# Microcontroller.net
KiCad netlist of a schematic drawn in Altium Designer
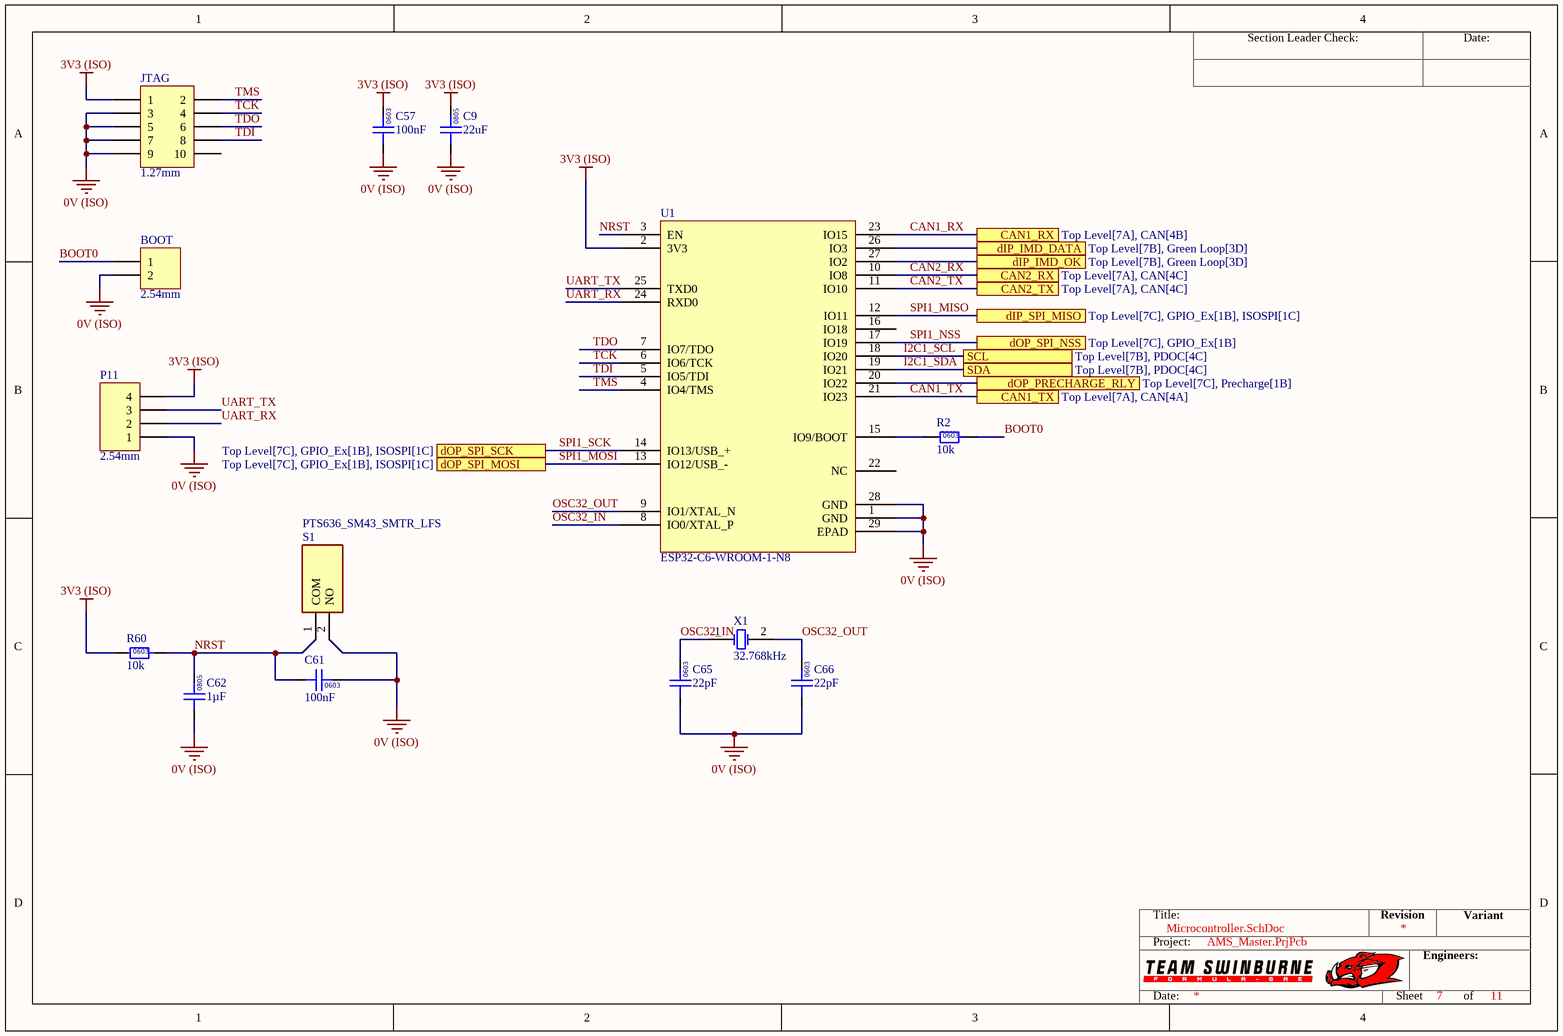
[diagram p0: Microcontroller.SchDoc]

(export (version "E")
  (design (tool "Eeschema 10.0.6"))
  (components
    (comp (ref "BOOT")
      (value "2.54mm")
      (footprint "TH 2.54mm Header 1x2")
      (fields (field (name "PART NUMBER") "TH 2.54mm Header 1x2") (field (name "CONTACT") "NA"))
      (libsource (lib "ts_standard_connectors") (part "Header 1x2"))
    )
    (comp (ref "C9")
      (value "22uF")
      (footprint "0805")
      (fields
        (field (name "PART NUMBER") "GRM21BR61A226ME51L")
        (field (name "MANUFACTURER") "muRata")
        (field (name "TOLERANCE") "20%")
      )
      (libsource (lib "ts_standard_library") (part "Capacitor 0805"))
    )
    (comp (ref "C57")
      (value "100nF")
      (footprint "0603")
      (fields
        (field (name "PART NUMBER") "GCM188L81H104KA57D")
        (field (name "MANUFACTURER") "muRata")
        (field (name "TOLERANCE") "±10%")
      )
      (libsource (lib "ts_standard_library") (part "Capacitor 0603"))
    )
    (comp (ref "C61")
      (value "100nF")
      (footprint "0603")
      (fields
        (field (name "PART NUMBER") "GCM188L81H104KA57D")
        (field (name "MANUFACTURER") "muRata")
        (field (name "TOLERANCE") "±10%")
      )
      (libsource (lib "ts_standard_library") (part "Capacitor 0603"))
    )
    (comp (ref "C62")
      (value "1µF")
      (footprint "0805")
      (fields
        (field (name "PART NUMBER") "GCM21BR71H105KA03L")
        (field (name "MANUFACTURER") "muRata")
        (field (name "TOLERANCE") "±10%")
      )
      (libsource (lib "ts_standard_library") (part "Capacitor 0805"))
    )
    (comp (ref "C65")
      (value "22pF")
      (footprint "0603")
      (fields
        (field (name "PART NUMBER") "GRM0335C1H220JA01D")
        (field (name "MANUFACTURER") "Murata Electronics")
        (field (name "TOLERANCE") "±5%")
      )
      (libsource (lib "ts_standard_library") (part "Capacitor 0603"))
    )
    (comp (ref "C66")
      (value "22pF")
      (footprint "0603")
      (fields
        (field (name "PART NUMBER") "GRM0335C1H220JA01D")
        (field (name "MANUFACTURER") "Murata Electronics")
        (field (name "TOLERANCE") "±5%")
      )
      (libsource (lib "ts_standard_library") (part "Capacitor 0603"))
    )
    (comp (ref "JTAG")
      (value "1.27mm")
      (footprint "3221-10-0300-00")
      (fields
        (field (name "PART NUMBER") "SMD 1.27mm Header 2x5 (3221-10-0300-00)")
        (field (name "CONTACT") "NA")
      )
      (libsource (lib "ts_standard_connectors") (part "Header 2x5"))
    )
    (comp (ref "P11")
      (value "2.54mm")
      (footprint "TH 2.54mm Header 1x4")
      (fields (field (name "PART NUMBER") "TH 2.54mm Header 1x4") (field (name "CONTACT") "NA"))
      (libsource (lib "ts_standard_connectors") (part "Header 1x4"))
    )
    (comp (ref "R2")
      (value "10k")
      (footprint "0603")
      (fields
        (field (name "PART NUMBER") "RC0603FR-0710KL")
        (field (name "MANUFACTURER") "YAGEO")
        (field (name "TOLERANCE") "0.01")
      )
      (libsource (lib "ts_standard_library") (part "Resistor 0603"))
    )
    (comp (ref "R60")
      (value "10k")
      (footprint "0603")
      (fields
        (field (name "PART NUMBER") "RC0603FR-0710KL")
        (field (name "MANUFACTURER") "YAGEO")
        (field (name "TOLERANCE") "0.01")
      )
      (libsource (lib "ts_standard_library") (part "Resistor 0603"))
    )
    (comp (ref "S1")
      (value "PTS636_SM43_SMTR_LFS")
      (footprint "SamacSys:PTS636SM43SMTRLFS")
      (description "Switch")
      (fields
        (field (name "MANUFACTURER_PART_NUMBER") "PTS636 SM43 SMTR LFS")
        (field (name "MOUSER PART NUMBER") "611-PTS636SM43SMTRLF")
      )
      (libsource (lib "*") (part "PTS636_SM43_SMTR_LFS"))
    )
    (comp (ref "U1")
      (value "ESP32-C6-WROOM-1-N8")
      (footprint "ESP32-C6-WROOM-1-N8")
      (description "RF TXRX MOD BT WIFI PCB TH SMD")
      (fields (field (name "MANUFACTURER") "Espressif"))
      (libsource (lib "ts_standard_library") (part "ESP32-C6-WROOM-1-N8"))
    )
    (comp (ref "X1")
      (value "32.768kHz")
      (footprint "EPSON 2-SMD")
      (fields
        (field (name "PART NUMBER") "FC-135 32.7680KA-A5")
        (field (name "MANUFACTURER") "EPSON")
        (field (name "DIGIKEY PART NUMBER") "SER4103TR-ND")
      )
      (libsource (lib "ts_standard_library") (part "Crystal"))
    )
  )
  (nets
    (net (code "1") (name "/BOOT0") (class "Default")
      (node (ref "BOOT") (pin "1") (pinfunction "1_1") (pintype "passive"))
      (node (ref "R2") (pin "2") (pinfunction "2_2") (pintype "passive"))
    )
    (net (code "2") (name "/CAN1_RX") (class "Default")
      (node (ref "U1") (pin "23") (pinfunction "IO15_23") (pintype "passive"))
    )
    (net (code "3") (name "/CAN1_TX") (class "Default")
      (node (ref "U1") (pin "21") (pinfunction "IO23_21") (pintype "passive"))
    )
    (net (code "4") (name "/CAN2_RX") (class "Default")
      (node (ref "U1") (pin "10") (pinfunction "IO8_10") (pintype "passive"))
    )
    (net (code "5") (name "/CAN2_TX") (class "Default")
      (node (ref "U1") (pin "11") (pinfunction "IO10_11") (pintype "passive"))
    )
    (net (code "6") (name "/I2C1_SCL") (class "Default")
      (node (ref "U1") (pin "18") (pinfunction "IO20_18") (pintype "passive"))
    )
    (net (code "7") (name "/I2C1_SDA") (class "Default")
      (node (ref "U1") (pin "19") (pinfunction "IO21_19") (pintype "passive"))
    )
    (net (code "8") (name "/NRST") (class "Default")
      (node (ref "C61") (pin "1") (pinfunction "1_1") (pintype "passive"))
      (node (ref "C62") (pin "2") (pinfunction "2_2") (pintype "passive"))
      (node (ref "R60") (pin "2") (pinfunction "2_2") (pintype "passive"))
      (node (ref "S1") (pin "1") (pinfunction "COM_1") (pintype "passive"))
      (node (ref "U1") (pin "3") (pinfunction "EN_3") (pintype "passive"))
    )
    (net (code "9") (name "/OSC32_IN") (class "Default")
      (node (ref "C65") (pin "2") (pinfunction "2_2") (pintype "passive"))
      (node (ref "U1") (pin "8") (pinfunction "IO0/XTAL_P_8") (pintype "passive"))
      (node (ref "X1") (pin "1") (pinfunction "OSC1_1") (pintype "passive"))
    )
    (net (code "10") (name "/OSC32_OUT") (class "Default")
      (node (ref "C66") (pin "2") (pinfunction "2_2") (pintype "passive"))
      (node (ref "U1") (pin "9") (pinfunction "IO1/XTAL_N_9") (pintype "passive"))
      (node (ref "X1") (pin "2") (pinfunction "OSC2_2") (pintype "passive"))
    )
    (net (code "11") (name "/SPI1_MISO") (class "Default")
      (node (ref "U1") (pin "12") (pinfunction "IO11_12") (pintype "passive"))
    )
    (net (code "12") (name "/SPI1_MOSI") (class "Default")
      (node (ref "U1") (pin "13") (pinfunction "IO12/USB_-_13") (pintype "passive"))
    )
    (net (code "13") (name "/SPI1_NSS") (class "Default")
      (node (ref "U1") (pin "17") (pinfunction "IO19_17") (pintype "passive"))
    )
    (net (code "14") (name "/SPI1_SCK") (class "Default")
      (node (ref "U1") (pin "14") (pinfunction "IO13/USB_+_14") (pintype "passive"))
    )
    (net (code "15") (name "/TCK") (class "Default")
      (node (ref "JTAG") (pin "4") (pinfunction "4_4") (pintype "passive"))
      (node (ref "U1") (pin "6") (pinfunction "IO6/TCK_6") (pintype "passive"))
    )
    (net (code "16") (name "/TDI") (class "Default")
      (node (ref "JTAG") (pin "8") (pinfunction "8_8") (pintype "passive"))
      (node (ref "U1") (pin "5") (pinfunction "IO5/TDI_5") (pintype "passive"))
    )
    (net (code "17") (name "/TDO") (class "Default")
      (node (ref "JTAG") (pin "6") (pinfunction "6_6") (pintype "passive"))
      (node (ref "U1") (pin "7") (pinfunction "IO7/TDO_7") (pintype "passive"))
    )
    (net (code "18") (name "/TMS") (class "Default")
      (node (ref "JTAG") (pin "2") (pinfunction "2_2") (pintype "passive"))
      (node (ref "U1") (pin "4") (pinfunction "IO4/TMS_4") (pintype "passive"))
    )
    (net (code "19") (name "/UART_RX") (class "Default")
      (node (ref "P11") (pin "2") (pinfunction "2_2") (pintype "passive"))
      (node (ref "U1") (pin "24") (pinfunction "RXD0_24") (pintype "passive"))
    )
    (net (code "20") (name "/UART_TX") (class "Default")
      (node (ref "P11") (pin "3") (pinfunction "3_3") (pintype "passive"))
      (node (ref "U1") (pin "25") (pinfunction "TXD0_25") (pintype "passive"))
    )
    (net (code "21") (name "/dIP_IMD_DATA") (class "Default")
      (node (ref "U1") (pin "26") (pinfunction "IO3_26") (pintype "passive"))
    )
    (net (code "22") (name "/dIP_IMD_OK") (class "Default")
      (node (ref "U1") (pin "27") (pinfunction "IO2_27") (pintype "passive"))
    )
    (net (code "23") (name "/dOP_PRECHARGE_RLY") (class "Default")
      (node (ref "U1") (pin "20") (pinfunction "IO22_20") (pintype "passive"))
    )
    (net (code "24") (name "0V (ISO)") (class "Default")
      (node (ref "BOOT") (pin "2") (pinfunction "2_2") (pintype "passive"))
      (node (ref "C57") (pin "1") (pinfunction "1_1") (pintype "passive"))
      (node (ref "C61") (pin "2") (pinfunction "2_2") (pintype "passive"))
      (node (ref "C62") (pin "1") (pinfunction "1_1") (pintype "passive"))
      (node (ref "C65") (pin "1") (pinfunction "1_1") (pintype "passive"))
      (node (ref "C66") (pin "1") (pinfunction "1_1") (pintype "passive"))
      (node (ref "C9") (pin "1") (pinfunction "1_1") (pintype "passive"))
      (node (ref "JTAG") (pin "3") (pinfunction "3_3") (pintype "passive"))
      (node (ref "JTAG") (pin "5") (pinfunction "5_5") (pintype "passive"))
      (node (ref "JTAG") (pin "7") (pinfunction "7_7") (pintype "passive"))
      (node (ref "JTAG") (pin "9") (pinfunction "9_9") (pintype "passive"))
      (node (ref "P11") (pin "1") (pinfunction "1_1") (pintype "passive"))
      (node (ref "S1") (pin "2") (pinfunction "NO_2") (pintype "passive"))
      (node (ref "U1") (pin "1") (pinfunction "GND_1") (pintype "passive"))
      (node (ref "U1") (pin "28") (pinfunction "GND_28") (pintype "passive"))
      (node (ref "U1") (pin "29") (pinfunction "EPAD_29") (pintype "passive"))
    )
    (net (code "25") (name "3V3 (ISO)") (class "Default")
      (node (ref "C57") (pin "2") (pinfunction "2_2") (pintype "passive"))
      (node (ref "C9") (pin "2") (pinfunction "2_2") (pintype "passive"))
      (node (ref "JTAG") (pin "1") (pinfunction "1_1") (pintype "passive"))
      (node (ref "P11") (pin "4") (pinfunction "4_4") (pintype "passive"))
      (node (ref "R60") (pin "1") (pinfunction "1_1") (pintype "passive"))
      (node (ref "U1") (pin "2") (pinfunction "3V3_2") (pintype "passive"))
    )
    (net (code "26") (name "Net-(U1-IO9{slash}BOOT)") (class "Default")
      (node (ref "R2") (pin "1") (pinfunction "1_1") (pintype "passive"))
      (node (ref "U1") (pin "15") (pinfunction "IO9/BOOT_15") (pintype "passive"))
    )
    (net (code "27") (name "unconnected-(JTAG-Pad10)") (class "Default")
      (node (ref "JTAG") (pin "10") (pinfunction "10_10") (pintype "passive"))
    )
    (net (code "28") (name "unconnected-(U1-IO18-Pad16)") (class "Default")
      (node (ref "U1") (pin "16") (pinfunction "IO18_16") (pintype "passive"))
    )
    (net (code "29") (name "unconnected-(U1-NC-Pad22)") (class "Default")
      (node (ref "U1") (pin "22") (pinfunction "NC_22") (pintype "passive"))
    )
  )
)
